# F4AIR.net
KiCad netlist of a schematic drawn in Altium Designer
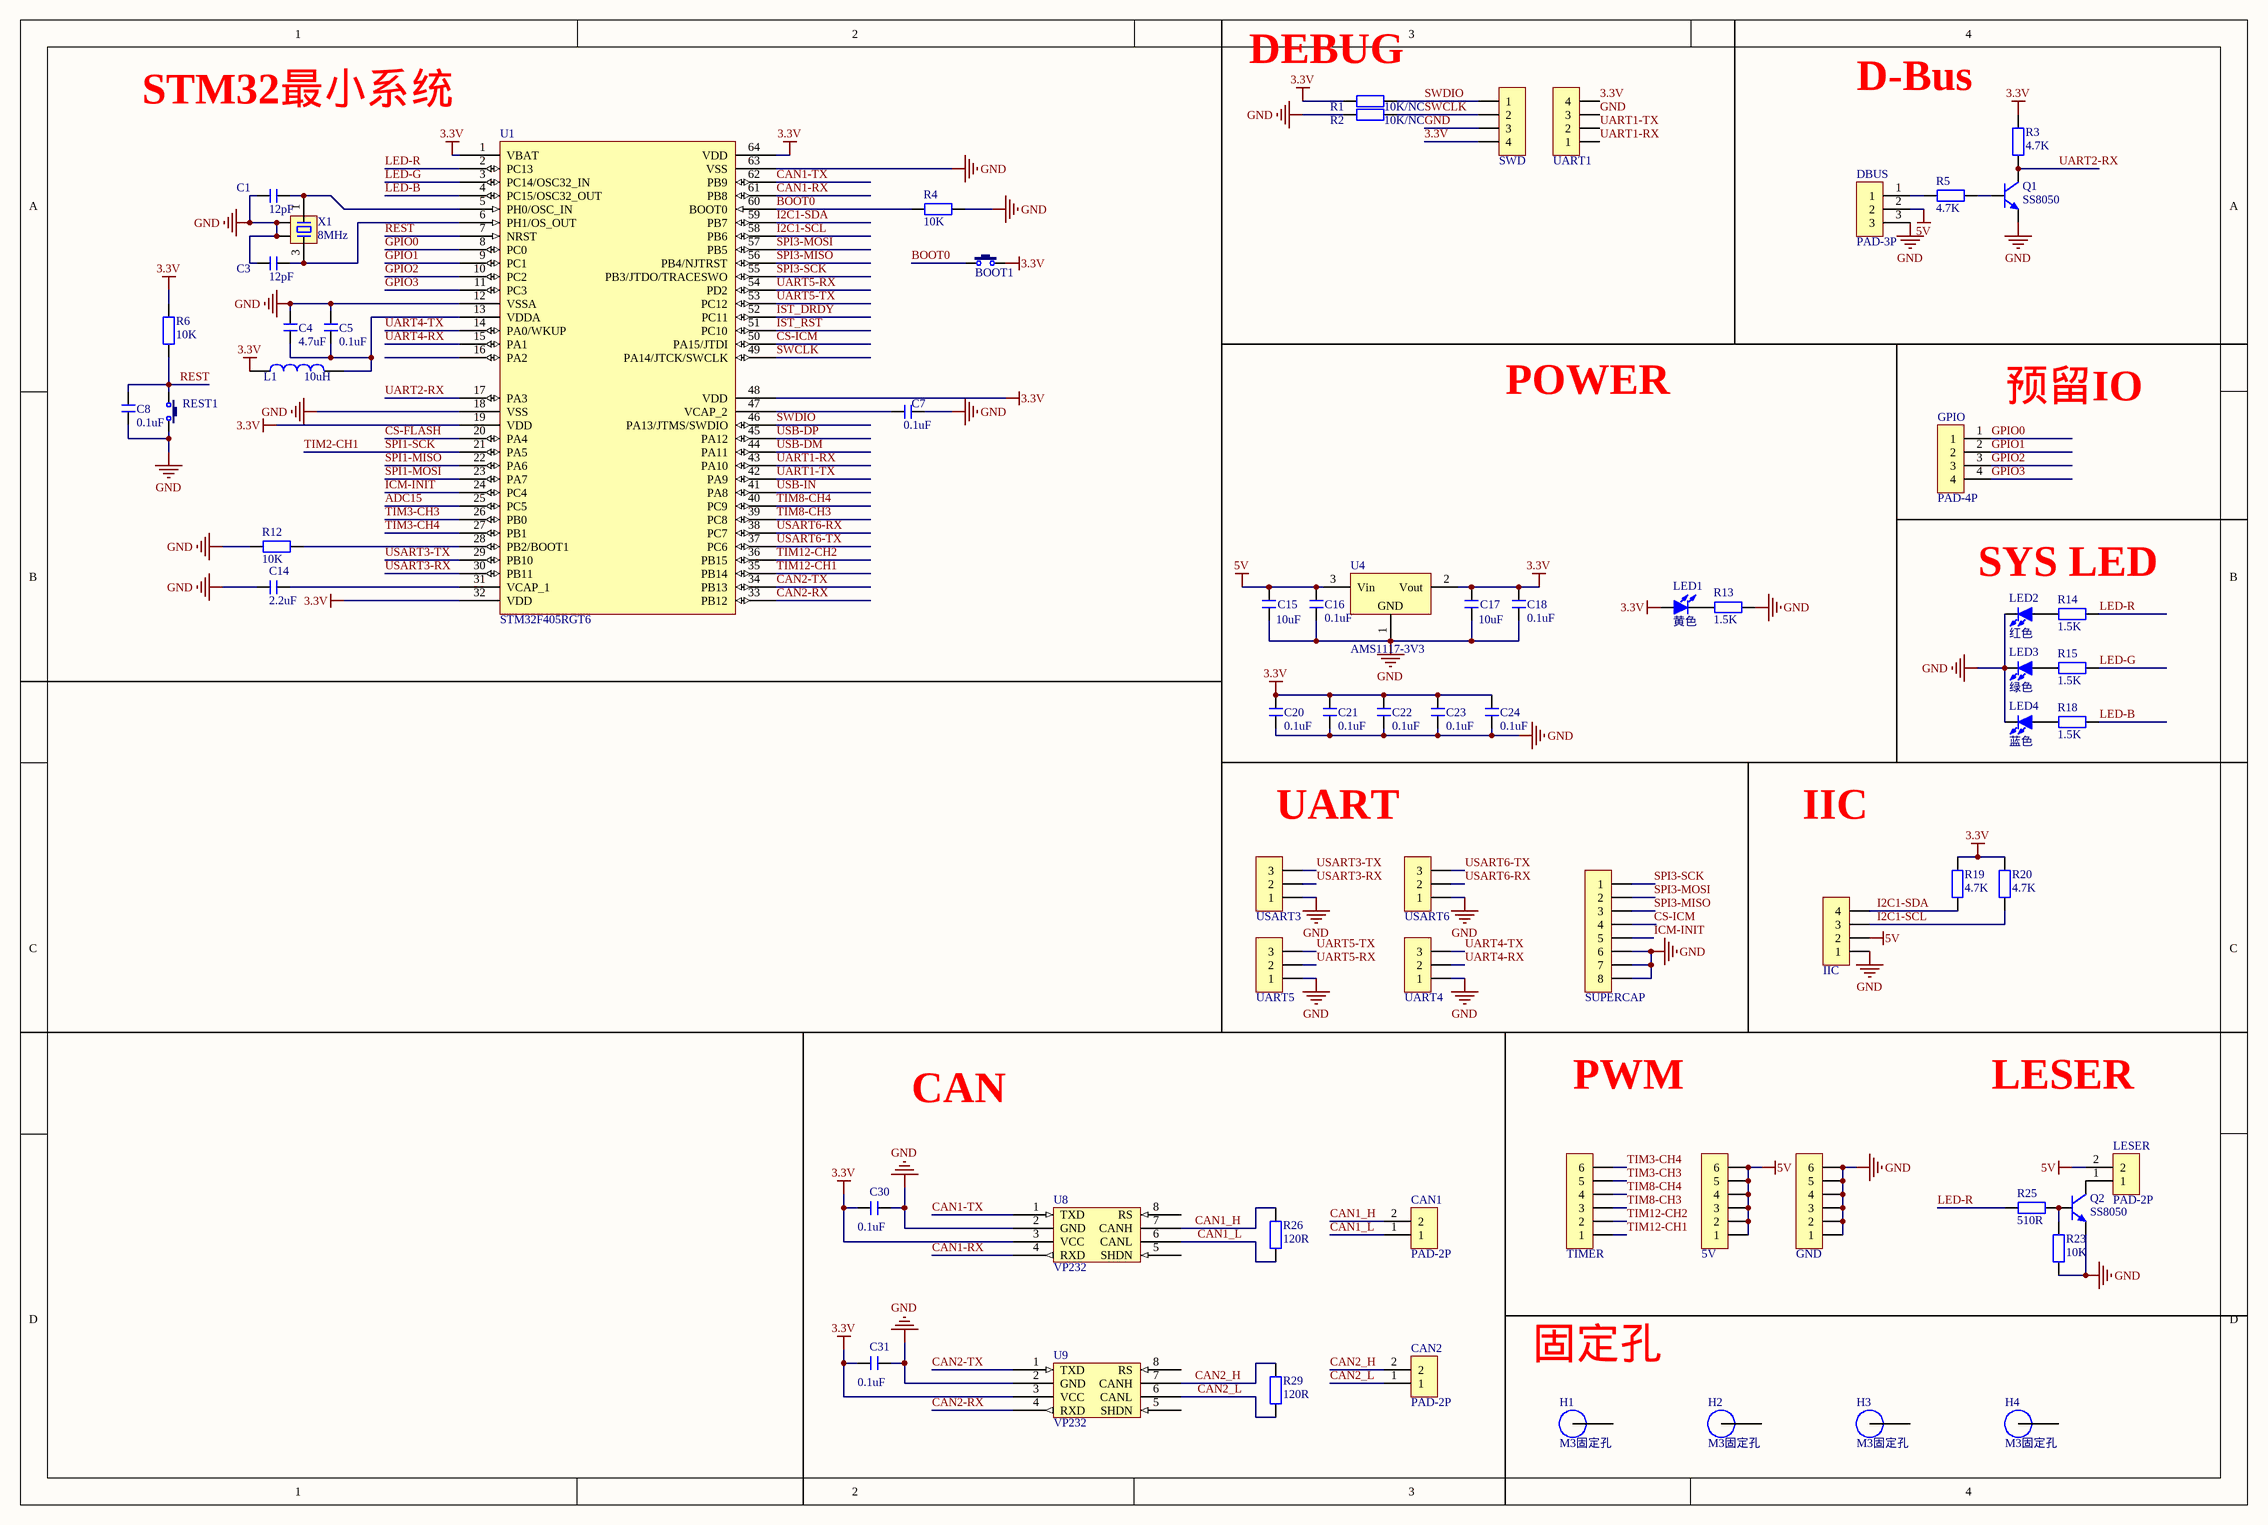
[diagram p0: F4AIR.SchDoc]

(export (version "E")
  (design (tool "Eeschema 10.0.6"))
  (components
    (comp (ref "5V")
      (value "HDR-1X6")
      (footprint "HDR2.54-LI-6P")
      (description "6P接插件")
      (fields (field (name "版权归属") "源创客"))
      (libsource (lib "*") (part "Header 6"))
    )
    (comp (ref "BOOT1")
      (value "3x6x5")
      (footprint "TSW SMD-3*6*5")
      (description "3x6轻触开关")
      (fields (field (name "版权归属") "源创客"))
      (libsource (lib "Schlib1") (part "TSW 3x6"))
    )
    (comp (ref "C1")
      (value "12pF")
      (footprint "C 0603_M")
      (description "无极性贴片电容")
      (fields (field (name "版权归属") "源创客"))
      (libsource (lib "Schlib1") (part "C"))
    )
    (comp (ref "C3")
      (value "12pF")
      (footprint "C 0603_M")
      (description "无极性贴片电容")
      (fields (field (name "版权归属") "源创客"))
      (libsource (lib "Schlib1") (part "C"))
    )
    (comp (ref "C4")
      (value "4.7uF")
      (footprint "C 0603_M")
      (description "无极性贴片电容")
      (fields (field (name "版权归属") "源创客"))
      (libsource (lib "Schlib1") (part "C"))
    )
    (comp (ref "C5")
      (value "0.1uF")
      (footprint "C 0603_M")
      (description "无极性贴片电容")
      (fields (field (name "版权归属") "源创客"))
      (libsource (lib "Schlib1") (part "C"))
    )
    (comp (ref "C7")
      (value "0.1uF")
      (footprint "C 0603_M")
      (description "无极性贴片电容")
      (fields (field (name "版权归属") "源创客"))
      (libsource (lib "Schlib1") (part "C"))
    )
    (comp (ref "C8")
      (value "0.1uF")
      (footprint "C 0603_M")
      (description "无极性贴片电容")
      (fields (field (name "版权归属") "源创客"))
      (libsource (lib "Schlib1") (part "C"))
    )
    (comp (ref "C14")
      (value "2.2uF")
      (footprint "C 0603_M")
      (description "无极性贴片电容")
      (fields (field (name "版权归属") "源创客"))
      (libsource (lib "Schlib1") (part "C"))
    )
    (comp (ref "C15")
      (value "10uF")
      (footprint "C 0805_M")
      (description "无极性贴片电容")
      (fields (field (name "版权归属") "源创客"))
      (libsource (lib "altium-import") (part "root_1_C_"))
    )
    (comp (ref "C16")
      (value "0.1uF")
      (footprint "C 0603_M")
      (description "无极性贴片电容")
      (fields (field (name "版权归属") "源创客"))
      (libsource (lib "Schlib1") (part "C"))
    )
    (comp (ref "C17")
      (value "10uF")
      (footprint "C 0805_M")
      (description "无极性贴片电容")
      (fields (field (name "版权归属") "源创客"))
      (libsource (lib "altium-import") (part "root_1_C_"))
    )
    (comp (ref "C18")
      (value "0.1uF")
      (footprint "C 0603_M")
      (description "无极性贴片电容")
      (fields (field (name "版权归属") "源创客"))
      (libsource (lib "Schlib1") (part "C"))
    )
    (comp (ref "C20")
      (value "0.1uF")
      (footprint "C 0603_M")
      (description "无极性贴片电容")
      (fields (field (name "版权归属") "源创客"))
      (libsource (lib "Schlib1") (part "C"))
    )
    (comp (ref "C21")
      (value "0.1uF")
      (footprint "C 0603_M")
      (description "无极性贴片电容")
      (fields (field (name "版权归属") "源创客"))
      (libsource (lib "Schlib1") (part "C"))
    )
    (comp (ref "C22")
      (value "0.1uF")
      (footprint "C 0603_M")
      (description "无极性贴片电容")
      (fields (field (name "版权归属") "源创客"))
      (libsource (lib "Schlib1") (part "C"))
    )
    (comp (ref "C23")
      (value "0.1uF")
      (footprint "C 0603_M")
      (description "无极性贴片电容")
      (fields (field (name "版权归属") "源创客"))
      (libsource (lib "Schlib1") (part "C"))
    )
    (comp (ref "C24")
      (value "0.1uF")
      (footprint "C 0603_M")
      (description "无极性贴片电容")
      (fields (field (name "版权归属") "源创客"))
      (libsource (lib "Schlib1") (part "C"))
    )
    (comp (ref "C30")
      (value "0.1uF")
      (footprint "C 0603_M")
      (description "无极性贴片电容")
      (fields (field (name "版权归属") "源创客"))
      (libsource (lib "Schlib1") (part "C"))
    )
    (comp (ref "C31")
      (value "0.1uF")
      (footprint "C 0603_M")
      (description "无极性贴片电容")
      (fields (field (name "版权归属") "源创客"))
      (libsource (lib "Schlib1") (part "C"))
    )
    (comp (ref "CAN1") (value "PAD-2P") (footprint "MX 1.25-WS-2P") (libsource (lib "F4AIR") (part "PAD-2P")))
    (comp (ref "CAN2") (value "PAD-2P") (footprint "MX 1.25-WS-2P") (libsource (lib "F4AIR") (part "PAD-2P")))
    (comp (ref "DBUS") (value "PAD-3P") (footprint "HDR2.54-WI-3P") (libsource (lib "F4AIR") (part "PAD-3P")))
    (comp (ref "GND")
      (value "HDR-1X6")
      (footprint "HDR2.54-LI-6P")
      (description "6P接插件")
      (fields (field (name "版权归属") "源创客"))
      (libsource (lib "*") (part "Header 6"))
    )
    (comp (ref "GPIO") (value "PAD-4P") (footprint "PAD-1.25-4P") (libsource (lib "F4AIR") (part "PAD-4P")))
    (comp (ref "H1")
      (value "M3固定孔")
      (footprint "M3x4_N")
      (description "铜柱孔")
      (fields (field (name "版权归属") "源创客"))
      (libsource (lib "F4AIR") (part "M3"))
    )
    (comp (ref "H2")
      (value "M3固定孔")
      (footprint "M3x4_N")
      (description "铜柱孔")
      (fields (field (name "版权归属") "源创客"))
      (libsource (lib "F4AIR") (part "M3"))
    )
    (comp (ref "H3")
      (value "M3固定孔")
      (footprint "M3x4_N")
      (description "铜柱孔")
      (fields (field (name "版权归属") "源创客"))
      (libsource (lib "F4AIR") (part "M3"))
    )
    (comp (ref "H4")
      (value "M3固定孔")
      (footprint "M3x4_N")
      (description "铜柱孔")
      (fields (field (name "版权归属") "源创客"))
      (libsource (lib "F4AIR") (part "M3"))
    )
    (comp (ref "IIC")
      (value "HDR-1X4")
      (footprint "HDR2.54-LI-4P")
      (description "HDR 2.54 -4P")
      (libsource (lib "核心板v2") (part "HDR 2.54 -4P_1"))
    )
    (comp (ref "L1")
      (value "10uH")
      (footprint "L 0603")
      (description "小功率贴片电感")
      (fields (field (name "版权归属") "源创客"))
      (libsource (lib "Schlib1") (part "L"))
    )
    (comp (ref "LED1")
      (value "黄色")
      (footprint "LED 0603Y")
      (description "贴片LED")
      (fields (field (name "版权归属") "源创客"))
      (libsource (lib "核心板v2") (part "LED-SMD"))
    )
    (comp (ref "LED2")
      (value "红色")
      (footprint "LED 0603R")
      (description "贴片LED")
      (fields (field (name "版权归属") "源创客"))
      (libsource (lib "核心板v2") (part "LED-SMD"))
    )
    (comp (ref "LED3")
      (value "绿色")
      (footprint "LED 0603G")
      (description "贴片LED")
      (fields (field (name "版权归属") "源创客"))
      (libsource (lib "核心板v2") (part "LED-SMD"))
    )
    (comp (ref "LED4")
      (value "蓝色")
      (footprint "LED 0603B")
      (description "贴片LED")
      (fields (field (name "版权归属") "源创客"))
      (libsource (lib "核心板v2") (part "LED-SMD"))
    )
    (comp (ref "LESER")
      (value "PAD-2P")
      (footprint "MX 1.25-WS-2P")
      (libsource (lib "F4AIR") (part "PAD-2P"))
    )
    (comp (ref "Q1")
      (value "SS8050")
      (footprint "SOT23-3M")
      (description "高频放大-NPN型")
      (libsource (lib "Schlib1") (part "8050-SMD"))
    )
    (comp (ref "Q2")
      (value "SS8050")
      (footprint "SOT23-3M")
      (description "高频放大-NPN型")
      (libsource (lib "核心板v2") (part "8050-SMD"))
    )
    (comp (ref "R1")
      (value "10K/NC")
      (footprint "R 0603_M")
      (description "贴片电阻")
      (fields (field (name "版权归属") "源创客"))
      (libsource (lib "Schlib1") (part "R"))
    )
    (comp (ref "R2")
      (value "10K/NC")
      (footprint "R 0603_M")
      (description "贴片电阻")
      (fields (field (name "版权归属") "源创客"))
      (libsource (lib "Schlib1") (part "R"))
    )
    (comp (ref "R3")
      (value "4.7K")
      (footprint "R 0603_M")
      (description "贴片电阻")
      (fields (field (name "版权归属") "源创客"))
      (libsource (lib "Schlib1") (part "R"))
    )
    (comp (ref "R4")
      (value "10K")
      (footprint "R 0603_M")
      (description "贴片电阻")
      (fields (field (name "版权归属") "源创客"))
      (libsource (lib "Schlib1") (part "R"))
    )
    (comp (ref "R5")
      (value "4.7K")
      (footprint "R 0603_M")
      (description "贴片电阻")
      (fields (field (name "版权归属") "源创客"))
      (libsource (lib "Schlib1") (part "R"))
    )
    (comp (ref "R6")
      (value "10K")
      (footprint "R 0603_M")
      (description "贴片电阻")
      (fields (field (name "版权归属") "源创客"))
      (libsource (lib "Schlib1") (part "R"))
    )
    (comp (ref "R12")
      (value "10K")
      (footprint "R 0603_M")
      (description "贴片电阻")
      (fields (field (name "版权归属") "源创客"))
      (libsource (lib "Schlib1") (part "R"))
    )
    (comp (ref "R13")
      (value "1.5K")
      (footprint "R 0603_M")
      (description "贴片电阻")
      (fields (field (name "版权归属") "源创客"))
      (libsource (lib "核心板v2") (part "R"))
    )
    (comp (ref "R14")
      (value "1.5K")
      (footprint "R 0603_M")
      (description "贴片电阻")
      (fields (field (name "版权归属") "源创客"))
      (libsource (lib "核心板v2") (part "R"))
    )
    (comp (ref "R15")
      (value "1.5K")
      (footprint "R 0603_M")
      (description "贴片电阻")
      (fields (field (name "版权归属") "源创客"))
      (libsource (lib "核心板v2") (part "R"))
    )
    (comp (ref "R18")
      (value "1.5K")
      (footprint "R 0603_M")
      (description "贴片电阻")
      (fields (field (name "版权归属") "源创客"))
      (libsource (lib "核心板v2") (part "R"))
    )
    (comp (ref "R19")
      (value "4.7K")
      (footprint "R 0603_M")
      (description "贴片电阻")
      (fields (field (name "版权归属") "源创客"))
      (libsource (lib "altium-import") (part "root_3_R_"))
    )
    (comp (ref "R20")
      (value "4.7K")
      (footprint "R 0603_M")
      (description "贴片电阻")
      (fields (field (name "版权归属") "源创客"))
      (libsource (lib "altium-import") (part "root_1_R_"))
    )
    (comp (ref "R23")
      (value "10K")
      (footprint "R 0603_M")
      (description "贴片电阻")
      (fields (field (name "版权归属") "源创客"))
      (libsource (lib "核心板v2") (part "R"))
    )
    (comp (ref "R25")
      (value "510R")
      (footprint "R 0603_M")
      (description "贴片电阻")
      (fields (field (name "版权归属") "源创客"))
      (libsource (lib "核心板v2") (part "R"))
    )
    (comp (ref "R26")
      (value "120R")
      (footprint "R 0603_M")
      (description "贴片电阻")
      (fields (field (name "版权归属") "源创客"))
      (libsource (lib "altium-import") (part "root_1_R_"))
    )
    (comp (ref "R29")
      (value "120R")
      (footprint "R 0603_M")
      (description "贴片电阻")
      (fields (field (name "版权归属") "源创客"))
      (libsource (lib "altium-import") (part "root_1_R_"))
    )
    (comp (ref "REST1")
      (value "3x6x5")
      (footprint "TSW SMD-3*6*5")
      (description "3x6轻触开关")
      (fields (field (name "版权归属") "源创客"))
      (libsource (lib "") (part "TSW 3x6_1"))
    )
    (comp (ref "SUPERCAP")
      (value "HDR-1X8")
      (footprint "MX 1.25-WS-6P")
      (description "HDR 2.54 -8P")
      (libsource (lib "cap") (part "HDR 2.54 -8P"))
    )
    (comp (ref "SWD")
      (value "HDR-1X4")
      (footprint "MX 1.25-WS-4P")
      (description "MX 1.25 -4P")
      (libsource (lib "Schlib1") (part "MX 1.25 -4P"))
    )
    (comp (ref "TIMER")
      (value "HDR-1X6")
      (footprint "HDR2.54-LI-6P")
      (description "6P接插件")
      (fields (field (name "版权归属") "源创客"))
      (libsource (lib "*") (part "Header 6"))
    )
    (comp (ref "U1")
      (value "STM32F405RGT6")
      (footprint "LQFP64")
      (libsource (lib "Schlib") (part "STM32F405RGT6"))
    )
    (comp (ref "U4")
      (value "AMS1117-3V3")
      (footprint "SOT-89")
      (description "三端稳压芯片")
      (fields (field (name "版权归属") "源创客"))
      (libsource (lib "F4AIR") (part "AMS1117"))
    )
    (comp (ref "U8")
      (value "VP232")
      (footprint "SOP8_M")
      (description "CAN芯片")
      (libsource (lib "核心板v2") (part "MAX3051EKA+T"))
    )
    (comp (ref "U9")
      (value "VP232")
      (footprint "SOP8_M")
      (description "CAN芯片")
      (libsource (lib "核心板v2") (part "MAX3051EKA+T"))
    )
    (comp (ref "UART1")
      (value "HDR-1X4")
      (footprint "MX 1.25-WS-4P")
      (description "HDR 2.54 -4P")
      (libsource (lib "核心板v2") (part "HDR 2.54 -4P_1"))
    )
    (comp (ref "UART4")
      (value "HDR-1X3")
      (footprint "MX 1.25-WS-3P")
      (description "HDR 2.54 -3P")
      (libsource (lib "Schlib1") (part "HDR 2.54 -3P"))
    )
    (comp (ref "UART5")
      (value "HDR-1X3")
      (footprint "MX 1.25-WS-3P")
      (description "HDR 2.54 -3P")
      (libsource (lib "Schlib1") (part "HDR 2.54 -3P"))
    )
    (comp (ref "USART3")
      (value "HDR-1X3")
      (footprint "MX 1.25-WS-3P")
      (description "HDR 2.54 -3P")
      (libsource (lib "Schlib1") (part "HDR 2.54 -3P"))
    )
    (comp (ref "USART6")
      (value "HDR-1X3")
      (footprint "MX 1.25-WS-3P")
      (description "HDR 2.54 -3P")
      (libsource (lib "Schlib1") (part "HDR 2.54 -3P"))
    )
    (comp (ref "X1")
      (value "8MHz")
      (footprint "OSC 3225-4P")
      (description "4脚无源晶振")
      (fields (field (name "版权归属") "源创客"))
      (libsource (lib "Schlib1") (part "XTAL-4P"))
    )
  )
  (nets
    (net (code "1") (name "/ADC15") (class "Default")
      (node (ref "U1") (pin "25") (pinfunction "PC5_25") (pintype "bidirectional"))
    )
    (net (code "2") (name "/BOOT0") (class "Default")
      (node (ref "BOOT1") (pin "1") (pinfunction "1_1") (pintype "passive"))
      (node (ref "R4") (pin "1") (pinfunction "1_1") (pintype "passive"))
      (node (ref "U1") (pin "60") (pinfunction "BOOT0_60") (pintype "input"))
    )
    (net (code "3") (name "/CAN1-RX") (class "Default")
      (node (ref "U1") (pin "61") (pinfunction "PB8_61") (pintype "bidirectional"))
      (node (ref "U8") (pin "4") (pinfunction "RXD_4") (pintype "output"))
    )
    (net (code "4") (name "/CAN1-TX") (class "Default")
      (node (ref "U1") (pin "62") (pinfunction "PB9_62") (pintype "bidirectional"))
      (node (ref "U8") (pin "1") (pinfunction "TXD_1") (pintype "input"))
    )
    (net (code "5") (name "/CAN1_H") (class "Default")
      (node (ref "CAN1") (pin "2") (pinfunction "2_2") (pintype "passive"))
      (node (ref "R26") (pin "2") (pinfunction "2_2") (pintype "passive"))
      (node (ref "U8") (pin "7") (pinfunction "CANH_7") (pintype "passive"))
    )
    (net (code "6") (name "/CAN1_L") (class "Default")
      (node (ref "CAN1") (pin "1") (pinfunction "1_1") (pintype "passive"))
      (node (ref "R26") (pin "1") (pinfunction "1_1") (pintype "passive"))
      (node (ref "U8") (pin "6") (pinfunction "CANL_6") (pintype "passive"))
    )
    (net (code "7") (name "/CAN2-RX") (class "Default")
      (node (ref "U1") (pin "33") (pinfunction "PB12_33") (pintype "bidirectional"))
      (node (ref "U9") (pin "4") (pinfunction "RXD_4") (pintype "output"))
    )
    (net (code "8") (name "/CAN2-TX") (class "Default")
      (node (ref "U1") (pin "34") (pinfunction "PB13_34") (pintype "bidirectional"))
      (node (ref "U9") (pin "1") (pinfunction "TXD_1") (pintype "input"))
    )
    (net (code "9") (name "/CAN2_H") (class "Default")
      (node (ref "CAN2") (pin "2") (pinfunction "2_2") (pintype "passive"))
      (node (ref "R29") (pin "2") (pinfunction "2_2") (pintype "passive"))
      (node (ref "U9") (pin "7") (pinfunction "CANH_7") (pintype "passive"))
    )
    (net (code "10") (name "/CAN2_L") (class "Default")
      (node (ref "CAN2") (pin "1") (pinfunction "1_1") (pintype "passive"))
      (node (ref "R29") (pin "1") (pinfunction "1_1") (pintype "passive"))
      (node (ref "U9") (pin "6") (pinfunction "CANL_6") (pintype "passive"))
    )
    (net (code "11") (name "/CS-FLASH") (class "Default")
      (node (ref "U1") (pin "20") (pinfunction "PA4_20") (pintype "bidirectional"))
    )
    (net (code "12") (name "/CS-ICM") (class "Default")
      (node (ref "SUPERCAP") (pin "4") (pinfunction "4_4") (pintype "passive"))
      (node (ref "U1") (pin "50") (pinfunction "PA15/JTDI_50") (pintype "bidirectional"))
    )
    (net (code "13") (name "/GPIO0") (class "Default")
      (node (ref "GPIO") (pin "1") (pinfunction "1_1") (pintype "passive"))
      (node (ref "U1") (pin "8") (pinfunction "PC0_8") (pintype "bidirectional"))
    )
    (net (code "14") (name "/GPIO1") (class "Default")
      (node (ref "GPIO") (pin "2") (pinfunction "2_2") (pintype "passive"))
      (node (ref "U1") (pin "9") (pinfunction "PC1_9") (pintype "bidirectional"))
    )
    (net (code "15") (name "/GPIO2") (class "Default")
      (node (ref "GPIO") (pin "3") (pinfunction "3_3") (pintype "passive"))
      (node (ref "U1") (pin "10") (pinfunction "PC2_10") (pintype "bidirectional"))
    )
    (net (code "16") (name "/GPIO3") (class "Default")
      (node (ref "GPIO") (pin "4") (pinfunction "4_4") (pintype "passive"))
      (node (ref "U1") (pin "11") (pinfunction "PC3_11") (pintype "bidirectional"))
    )
    (net (code "17") (name "/I2C1-SCL") (class "Default")
      (node (ref "IIC") (pin "3") (pinfunction "3_3") (pintype "passive"))
      (node (ref "R20") (pin "1") (pinfunction "1_1") (pintype "passive"))
      (node (ref "U1") (pin "58") (pinfunction "PB6_58") (pintype "bidirectional"))
    )
    (net (code "18") (name "/I2C1-SDA") (class "Default")
      (node (ref "IIC") (pin "4") (pinfunction "4_4") (pintype "passive"))
      (node (ref "R19") (pin "2") (pinfunction "2_2") (pintype "passive"))
      (node (ref "U1") (pin "59") (pinfunction "PB7_59") (pintype "bidirectional"))
    )
    (net (code "19") (name "/ICM-INIT") (class "Default")
      (node (ref "SUPERCAP") (pin "5") (pinfunction "5_5") (pintype "passive"))
      (node (ref "U1") (pin "24") (pinfunction "PC4_24") (pintype "bidirectional"))
    )
    (net (code "20") (name "/IST_DRDY") (class "Default")
      (node (ref "U1") (pin "52") (pinfunction "PC11_52") (pintype "bidirectional"))
    )
    (net (code "21") (name "/IST_RST") (class "Default")
      (node (ref "U1") (pin "51") (pinfunction "PC10_51") (pintype "bidirectional"))
    )
    (net (code "22") (name "/LED-B") (class "Default")
      (node (ref "R18") (pin "2") (pinfunction "2_2") (pintype "passive"))
      (node (ref "U1") (pin "4") (pinfunction "PC15/OSC32_OUT_4") (pintype "bidirectional"))
    )
    (net (code "23") (name "/LED-G") (class "Default")
      (node (ref "R15") (pin "2") (pinfunction "2_2") (pintype "passive"))
      (node (ref "U1") (pin "3") (pinfunction "PC14/OSC32_IN_3") (pintype "bidirectional"))
    )
    (net (code "24") (name "/LED-R") (class "Default")
      (node (ref "R14") (pin "2") (pinfunction "2_2") (pintype "passive"))
      (node (ref "R25") (pin "1") (pinfunction "1_1") (pintype "passive"))
      (node (ref "U1") (pin "2") (pinfunction "PC13_2") (pintype "bidirectional"))
    )
    (net (code "25") (name "/REST") (class "Default")
      (node (ref "C8") (pin "2") (pinfunction "2_2") (pintype "passive"))
      (node (ref "R6") (pin "1") (pinfunction "1_1") (pintype "passive"))
      (node (ref "REST1") (pin "1") (pinfunction "1_1") (pintype "passive"))
      (node (ref "U1") (pin "7") (pinfunction "NRST_7") (pintype "input"))
    )
    (net (code "26") (name "/SPI1-MISO") (class "Default")
      (node (ref "U1") (pin "22") (pinfunction "PA6_22") (pintype "bidirectional"))
    )
    (net (code "27") (name "/SPI1-MOSI") (class "Default")
      (node (ref "U1") (pin "23") (pinfunction "PA7_23") (pintype "bidirectional"))
    )
    (net (code "28") (name "/SPI1-SCK") (class "Default")
      (node (ref "U1") (pin "21") (pinfunction "PA5_21") (pintype "bidirectional"))
    )
    (net (code "29") (name "/SPI3-MISO") (class "Default")
      (node (ref "SUPERCAP") (pin "3") (pinfunction "3_3") (pintype "passive"))
      (node (ref "U1") (pin "56") (pinfunction "PB4/NJTRST_56") (pintype "bidirectional"))
    )
    (net (code "30") (name "/SPI3-MOSI") (class "Default")
      (node (ref "SUPERCAP") (pin "2") (pinfunction "2_2") (pintype "passive"))
      (node (ref "U1") (pin "57") (pinfunction "PB5_57") (pintype "bidirectional"))
    )
    (net (code "31") (name "/SPI3-SCK") (class "Default")
      (node (ref "SUPERCAP") (pin "1") (pinfunction "1_1") (pintype "passive"))
      (node (ref "U1") (pin "55") (pinfunction "PB3/JTDO/TRACESWO_55") (pintype "bidirectional"))
    )
    (net (code "32") (name "/SWCLK") (class "Default")
      (node (ref "R2") (pin "2") (pinfunction "2_2") (pintype "passive"))
      (node (ref "SWD") (pin "2") (pinfunction "2_2") (pintype "passive"))
      (node (ref "U1") (pin "49") (pinfunction "PA14/JTCK/SWCLK_49") (pintype "bidirectional"))
    )
    (net (code "33") (name "/SWDIO") (class "Default")
      (node (ref "R1") (pin "2") (pinfunction "2_2") (pintype "passive"))
      (node (ref "SWD") (pin "1") (pinfunction "1_1") (pintype "passive"))
      (node (ref "U1") (pin "46") (pinfunction "PA13/JTMS/SWDIO_46") (pintype "bidirectional"))
    )
    (net (code "34") (name "/TIM3-CH3") (class "Default")
      (node (ref "TIMER") (pin "5") (pinfunction "5_5") (pintype "passive"))
      (node (ref "U1") (pin "26") (pinfunction "PB0_26") (pintype "bidirectional"))
    )
    (net (code "35") (name "/TIM3-CH4") (class "Default")
      (node (ref "TIMER") (pin "6") (pinfunction "6_6") (pintype "passive"))
      (node (ref "U1") (pin "27") (pinfunction "PB1_27") (pintype "bidirectional"))
    )
    (net (code "36") (name "/TIM8-CH3") (class "Default")
      (node (ref "TIMER") (pin "3") (pinfunction "3_3") (pintype "passive"))
      (node (ref "U1") (pin "39") (pinfunction "PC8_39") (pintype "bidirectional"))
    )
    (net (code "37") (name "/TIM8-CH4") (class "Default")
      (node (ref "TIMER") (pin "4") (pinfunction "4_4") (pintype "passive"))
      (node (ref "U1") (pin "40") (pinfunction "PC9_40") (pintype "bidirectional"))
    )
    (net (code "38") (name "/TIM12-CH1") (class "Default")
      (node (ref "TIMER") (pin "1") (pinfunction "1_1") (pintype "passive"))
      (node (ref "U1") (pin "35") (pinfunction "PB14_35") (pintype "bidirectional"))
    )
    (net (code "39") (name "/TIM12-CH2") (class "Default")
      (node (ref "TIMER") (pin "2") (pinfunction "2_2") (pintype "passive"))
      (node (ref "U1") (pin "36") (pinfunction "PB15_36") (pintype "bidirectional"))
    )
    (net (code "40") (name "/UART1-RX") (class "Default")
      (node (ref "U1") (pin "43") (pinfunction "PA10_43") (pintype "bidirectional"))
      (node (ref "UART1") (pin "1") (pinfunction "1_1") (pintype "passive"))
    )
    (net (code "41") (name "/UART1-TX") (class "Default")
      (node (ref "U1") (pin "42") (pinfunction "PA9_42") (pintype "bidirectional"))
      (node (ref "UART1") (pin "2") (pinfunction "2_2") (pintype "passive"))
    )
    (net (code "42") (name "/UART2-RX") (class "Default")
      (node (ref "Q1") (pin "3") (pinfunction "C_3") (pintype "passive"))
      (node (ref "R3") (pin "1") (pinfunction "1_1") (pintype "passive"))
      (node (ref "U1") (pin "17") (pinfunction "PA3_17") (pintype "bidirectional"))
    )
    (net (code "43") (name "/UART4-RX") (class "Default")
      (node (ref "U1") (pin "15") (pinfunction "PA1_15") (pintype "bidirectional"))
      (node (ref "UART4") (pin "2") (pinfunction "2_2") (pintype "passive"))
    )
    (net (code "44") (name "/UART4-TX") (class "Default")
      (node (ref "U1") (pin "14") (pinfunction "PA0/WKUP_14") (pintype "bidirectional"))
      (node (ref "UART4") (pin "3") (pinfunction "3_3") (pintype "passive"))
    )
    (net (code "45") (name "/UART5-RX") (class "Default")
      (node (ref "U1") (pin "54") (pinfunction "PD2_54") (pintype "bidirectional"))
      (node (ref "UART5") (pin "2") (pinfunction "2_2") (pintype "passive"))
    )
    (net (code "46") (name "/UART5-TX") (class "Default")
      (node (ref "U1") (pin "53") (pinfunction "PC12_53") (pintype "bidirectional"))
      (node (ref "UART5") (pin "3") (pinfunction "3_3") (pintype "passive"))
    )
    (net (code "47") (name "/USART3-RX") (class "Default")
      (node (ref "U1") (pin "30") (pinfunction "PB11_30") (pintype "bidirectional"))
      (node (ref "USART3") (pin "2") (pinfunction "2_2") (pintype "passive"))
    )
    (net (code "48") (name "/USART3-TX") (class "Default")
      (node (ref "U1") (pin "29") (pinfunction "PB10_29") (pintype "bidirectional"))
      (node (ref "USART3") (pin "3") (pinfunction "3_3") (pintype "passive"))
    )
    (net (code "49") (name "/USART6-RX") (class "Default")
      (node (ref "U1") (pin "38") (pinfunction "PC7_38") (pintype "bidirectional"))
      (node (ref "USART6") (pin "2") (pinfunction "2_2") (pintype "passive"))
    )
    (net (code "50") (name "/USART6-TX") (class "Default")
      (node (ref "U1") (pin "37") (pinfunction "PC6_37") (pintype "bidirectional"))
      (node (ref "USART6") (pin "3") (pinfunction "3_3") (pintype "passive"))
    )
    (net (code "51") (name "/USB-DM") (class "Default")
      (node (ref "U1") (pin "44") (pinfunction "PA11_44") (pintype "bidirectional"))
    )
    (net (code "52") (name "/USB-DP") (class "Default")
      (node (ref "U1") (pin "45") (pinfunction "PA12_45") (pintype "bidirectional"))
    )
    (net (code "53") (name "/USB-IN") (class "Default")
      (node (ref "U1") (pin "41") (pinfunction "PA8_41") (pintype "bidirectional"))
    )
    (net (code "54") (name "3.3V") (class "Default")
      (node (ref "BOOT1") (pin "2") (pinfunction "2_2") (pintype "passive"))
      (node (ref "C17") (pin "2") (pinfunction "2_2") (pintype "passive"))
      (node (ref "C18") (pin "1") (pinfunction "1_1") (pintype "passive"))
      (node (ref "C20") (pin "1") (pinfunction "1_1") (pintype "passive"))
      (node (ref "C21") (pin "1") (pinfunction "1_1") (pintype "passive"))
      (node (ref "C22") (pin "1") (pinfunction "1_1") (pintype "passive"))
      (node (ref "C23") (pin "1") (pinfunction "1_1") (pintype "passive"))
      (node (ref "C24") (pin "1") (pinfunction "1_1") (pintype "passive"))
      (node (ref "C30") (pin "2") (pinfunction "2_2") (pintype "passive"))
      (node (ref "C31") (pin "2") (pinfunction "2_2") (pintype "passive"))
      (node (ref "L1") (pin "1") (pinfunction "1_1") (pintype "passive"))
      (node (ref "LED1") (pin "1") (pinfunction "A_1") (pintype "passive"))
      (node (ref "R1") (pin "1") (pinfunction "1_1") (pintype "passive"))
      (node (ref "R19") (pin "1") (pinfunction "1_1") (pintype "passive"))
      (node (ref "R20") (pin "2") (pinfunction "2_2") (pintype "passive"))
      (node (ref "R3") (pin "2") (pinfunction "2_2") (pintype "passive"))
      (node (ref "R6") (pin "2") (pinfunction "2_2") (pintype "passive"))
      (node (ref "SWD") (pin "4") (pinfunction "4_4") (pintype "passive"))
      (node (ref "U1") (pin "1") (pinfunction "VBAT_1") (pintype "power_in"))
      (node (ref "U1") (pin "19") (pinfunction "VDD_19") (pintype "power_in"))
      (node (ref "U1") (pin "32") (pinfunction "VDD_32") (pintype "power_in"))
      (node (ref "U1") (pin "48") (pinfunction "VDD_48") (pintype "power_in"))
      (node (ref "U1") (pin "64") (pinfunction "VDD_64") (pintype "power_in"))
      (node (ref "U4") (pin "2") (pinfunction "Vout_2") (pintype "passive"))
      (node (ref "U8") (pin "3") (pinfunction "VCC_3") (pintype "power_in"))
      (node (ref "U9") (pin "3") (pinfunction "VCC_3") (pintype "power_in"))
      (node (ref "UART1") (pin "4") (pinfunction "4_4") (pintype "passive"))
    )
    (net (code "55") (name "5V") (class "Default")
      (node (ref "5V") (pin "1") (pinfunction "1_1") (pintype "passive"))
      (node (ref "5V") (pin "2") (pinfunction "2_2") (pintype "passive"))
      (node (ref "5V") (pin "3") (pinfunction "3_3") (pintype "passive"))
      (node (ref "5V") (pin "4") (pinfunction "4_4") (pintype "passive"))
      (node (ref "5V") (pin "5") (pinfunction "5_5") (pintype "passive"))
      (node (ref "5V") (pin "6") (pinfunction "6_6") (pintype "passive"))
      (node (ref "C15") (pin "2") (pinfunction "2_2") (pintype "passive"))
      (node (ref "C16") (pin "1") (pinfunction "1_1") (pintype "passive"))
      (node (ref "DBUS") (pin "2") (pinfunction "2_2") (pintype "passive"))
      (node (ref "IIC") (pin "2") (pinfunction "2_2") (pintype "passive"))
      (node (ref "LESER") (pin "2") (pinfunction "2_2") (pintype "passive"))
      (node (ref "U4") (pin "3") (pinfunction "Vin_3") (pintype "passive"))
    )
    (net (code "56") (name "GND") (class "Default")
      (node (ref "C1") (pin "1") (pinfunction "1_1") (pintype "passive"))
      (node (ref "C14") (pin "1") (pinfunction "1_1") (pintype "passive"))
      (node (ref "C15") (pin "1") (pinfunction "1_1") (pintype "passive"))
      (node (ref "C16") (pin "2") (pinfunction "2_2") (pintype "passive"))
      (node (ref "C17") (pin "1") (pinfunction "1_1") (pintype "passive"))
      (node (ref "C18") (pin "2") (pinfunction "2_2") (pintype "passive"))
      (node (ref "C20") (pin "2") (pinfunction "2_2") (pintype "passive"))
      (node (ref "C21") (pin "2") (pinfunction "2_2") (pintype "passive"))
      (node (ref "C22") (pin "2") (pinfunction "2_2") (pintype "passive"))
      (node (ref "C23") (pin "2") (pinfunction "2_2") (pintype "passive"))
      (node (ref "C24") (pin "2") (pinfunction "2_2") (pintype "passive"))
      (node (ref "C3") (pin "1") (pinfunction "1_1") (pintype "passive"))
      (node (ref "C30") (pin "1") (pinfunction "1_1") (pintype "passive"))
      (node (ref "C31") (pin "1") (pinfunction "1_1") (pintype "passive"))
      (node (ref "C4") (pin "2") (pinfunction "2_2") (pintype "passive"))
      (node (ref "C5") (pin "2") (pinfunction "2_2") (pintype "passive"))
      (node (ref "C7") (pin "2") (pinfunction "2_2") (pintype "passive"))
      (node (ref "C8") (pin "1") (pinfunction "1_1") (pintype "passive"))
      (node (ref "DBUS") (pin "3") (pinfunction "3_3") (pintype "passive"))
      (node (ref "GND") (pin "1") (pinfunction "1_1") (pintype "passive"))
      (node (ref "GND") (pin "2") (pinfunction "2_2") (pintype "passive"))
      (node (ref "GND") (pin "3") (pinfunction "3_3") (pintype "passive"))
      (node (ref "GND") (pin "4") (pinfunction "4_4") (pintype "passive"))
      (node (ref "GND") (pin "5") (pinfunction "5_5") (pintype "passive"))
      (node (ref "GND") (pin "6") (pinfunction "6_6") (pintype "passive"))
      (node (ref "IIC") (pin "1") (pinfunction "1_1") (pintype "passive"))
      (node (ref "LED2") (pin "2") (pinfunction "K_2") (pintype "passive"))
      (node (ref "LED3") (pin "2") (pinfunction "K_2") (pintype "passive"))
      (node (ref "LED4") (pin "2") (pinfunction "K_2") (pintype "passive"))
      (node (ref "Q1") (pin "2") (pinfunction "E_2") (pintype "passive"))
      (node (ref "Q2") (pin "2") (pinfunction "E_2") (pintype "passive"))
      (node (ref "R12") (pin "1") (pinfunction "1_1") (pintype "passive"))
      (node (ref "R13") (pin "2") (pinfunction "2_2") (pintype "passive"))
      (node (ref "R2") (pin "1") (pinfunction "1_1") (pintype "passive"))
      (node (ref "R23") (pin "1") (pinfunction "1_1") (pintype "passive"))
      (node (ref "R4") (pin "2") (pinfunction "2_2") (pintype "passive"))
      (node (ref "REST1") (pin "2") (pinfunction "2_2") (pintype "passive"))
      (node (ref "SUPERCAP") (pin "6") (pinfunction "6_6") (pintype "passive"))
      (node (ref "SUPERCAP") (pin "7") (pinfunction "7_7") (pintype "passive"))
      (node (ref "SUPERCAP") (pin "8") (pinfunction "8_8") (pintype "passive"))
      (node (ref "SWD") (pin "3") (pinfunction "3_3") (pintype "passive"))
      (node (ref "U1") (pin "12") (pinfunction "VSSA_12") (pintype "power_in"))
      (node (ref "U1") (pin "18") (pinfunction "VSS_18") (pintype "power_in"))
      (node (ref "U1") (pin "63") (pinfunction "VSS_63") (pintype "power_in"))
      (node (ref "U4") (pin "1") (pinfunction "GND_1") (pintype "passive"))
      (node (ref "U8") (pin "2") (pinfunction "GND_2") (pintype "power_in"))
      (node (ref "U9") (pin "2") (pinfunction "GND_2") (pintype "power_in"))
      (node (ref "UART1") (pin "3") (pinfunction "3_3") (pintype "passive"))
      (node (ref "UART4") (pin "1") (pinfunction "1_1") (pintype "passive"))
      (node (ref "UART5") (pin "1") (pinfunction "1_1") (pintype "passive"))
      (node (ref "USART3") (pin "1") (pinfunction "1_1") (pintype "passive"))
      (node (ref "USART6") (pin "1") (pinfunction "1_1") (pintype "passive"))
      (node (ref "X1") (pin "2") (pinfunction "2_2") (pintype "passive"))
      (node (ref "X1") (pin "4") (pinfunction "4_4") (pintype "passive"))
    )
    (net (code "57") (name "Net-(DBUS-Pad1)") (class "Default")
      (node (ref "DBUS") (pin "1") (pinfunction "1_1") (pintype "passive"))
      (node (ref "R5") (pin "1") (pinfunction "1_1") (pintype "passive"))
    )
    (net (code "58") (name "Net-(LED1-K)") (class "Default")
      (node (ref "LED1") (pin "2") (pinfunction "K_2") (pintype "passive"))
      (node (ref "R13") (pin "1") (pinfunction "1_1") (pintype "passive"))
    )
    (net (code "59") (name "Net-(LED2-A)") (class "Default")
      (node (ref "LED2") (pin "1") (pinfunction "A_1") (pintype "passive"))
      (node (ref "R14") (pin "1") (pinfunction "1_1") (pintype "passive"))
    )
    (net (code "60") (name "Net-(LED3-A)") (class "Default")
      (node (ref "LED3") (pin "1") (pinfunction "A_1") (pintype "passive"))
      (node (ref "R15") (pin "1") (pinfunction "1_1") (pintype "passive"))
    )
    (net (code "61") (name "Net-(LED4-A)") (class "Default")
      (node (ref "LED4") (pin "1") (pinfunction "A_1") (pintype "passive"))
      (node (ref "R18") (pin "1") (pinfunction "1_1") (pintype "passive"))
    )
    (net (code "62") (name "Net-(Q1-B)") (class "Default")
      (node (ref "Q1") (pin "1") (pinfunction "B_1") (pintype "passive"))
      (node (ref "R5") (pin "2") (pinfunction "2_2") (pintype "passive"))
    )
    (net (code "63") (name "Net-(Q2-B)") (class "Default")
      (node (ref "Q2") (pin "1") (pinfunction "B_1") (pintype "passive"))
      (node (ref "R23") (pin "2") (pinfunction "2_2") (pintype "passive"))
      (node (ref "R25") (pin "2") (pinfunction "2_2") (pintype "passive"))
    )
    (net (code "64") (name "Net-(Q2-C)") (class "Default")
      (node (ref "LESER") (pin "1") (pinfunction "1_1") (pintype "passive"))
      (node (ref "Q2") (pin "3") (pinfunction "C_3") (pintype "passive"))
    )
    (net (code "65") (name "Net-(U1-PB2{slash}BOOT1)") (class "Default")
      (node (ref "R12") (pin "2") (pinfunction "2_2") (pintype "passive"))
      (node (ref "U1") (pin "28") (pinfunction "PB2/BOOT1_28") (pintype "bidirectional"))
    )
    (net (code "66") (name "Net-(U1-PH0{slash}OSC_IN)") (class "Default")
      (node (ref "C1") (pin "2") (pinfunction "2_2") (pintype "passive"))
      (node (ref "U1") (pin "5") (pinfunction "PH0/OSC_IN_5") (pintype "input"))
      (node (ref "X1") (pin "1") (pinfunction "1_1") (pintype "passive"))
    )
    (net (code "67") (name "Net-(U1-PH1{slash}OS_OUT)") (class "Default")
      (node (ref "C3") (pin "2") (pinfunction "2_2") (pintype "passive"))
      (node (ref "U1") (pin "6") (pinfunction "PH1/OS_OUT_6") (pintype "input"))
      (node (ref "X1") (pin "3") (pinfunction "3_3") (pintype "passive"))
    )
    (net (code "68") (name "Net-(U1-VCAP_1)") (class "Default")
      (node (ref "C14") (pin "2") (pinfunction "2_2") (pintype "passive"))
      (node (ref "U1") (pin "31") (pinfunction "VCAP_1_31") (pintype "passive"))
    )
    (net (code "69") (name "Net-(U1-VCAP_2)") (class "Default")
      (node (ref "C7") (pin "1") (pinfunction "1_1") (pintype "passive"))
      (node (ref "U1") (pin "47") (pinfunction "VCAP_2_47") (pintype "passive"))
    )
    (net (code "70") (name "Net-(U1-VDDA)") (class "Default")
      (node (ref "C4") (pin "1") (pinfunction "1_1") (pintype "passive"))
      (node (ref "C5") (pin "1") (pinfunction "1_1") (pintype "passive"))
      (node (ref "L1") (pin "2") (pinfunction "2_2") (pintype "passive"))
      (node (ref "U1") (pin "13") (pinfunction "VDDA_13") (pintype "power_in"))
    )
    (net (code "71") (name "unconnected-(H1-Pad1)") (class "Default")
      (node (ref "H1") (pin "1") (pinfunction "1_1") (pintype "passive"))
    )
    (net (code "72") (name "unconnected-(H2-Pad1)") (class "Default")
      (node (ref "H2") (pin "1") (pinfunction "1_1") (pintype "passive"))
    )
    (net (code "73") (name "unconnected-(H3-Pad1)") (class "Default")
      (node (ref "H3") (pin "1") (pinfunction "1_1") (pintype "passive"))
    )
    (net (code "74") (name "unconnected-(H4-Pad1)") (class "Default")
      (node (ref "H4") (pin "1") (pinfunction "1_1") (pintype "passive"))
    )
    (net (code "75") (name "unconnected-(U1-PA2-Pad16)") (class "Default")
      (node (ref "U1") (pin "16") (pinfunction "PA2_16") (pintype "bidirectional"))
    )
    (net (code "76") (name "unconnected-(U8-RS-Pad8)") (class "Default")
      (node (ref "U8") (pin "8") (pinfunction "RS_8") (pintype "input"))
    )
    (net (code "77") (name "unconnected-(U8-SHDN-Pad5)") (class "Default")
      (node (ref "U8") (pin "5") (pinfunction "SHDN_5") (pintype "input"))
    )
    (net (code "78") (name "unconnected-(U9-RS-Pad8)") (class "Default")
      (node (ref "U9") (pin "8") (pinfunction "RS_8") (pintype "input"))
    )
    (net (code "79") (name "unconnected-(U9-SHDN-Pad5)") (class "Default")
      (node (ref "U9") (pin "5") (pinfunction "SHDN_5") (pintype "input"))
    )
  )
)
